# AMP.net
KiCad netlist of a schematic drawn in Altium Designer
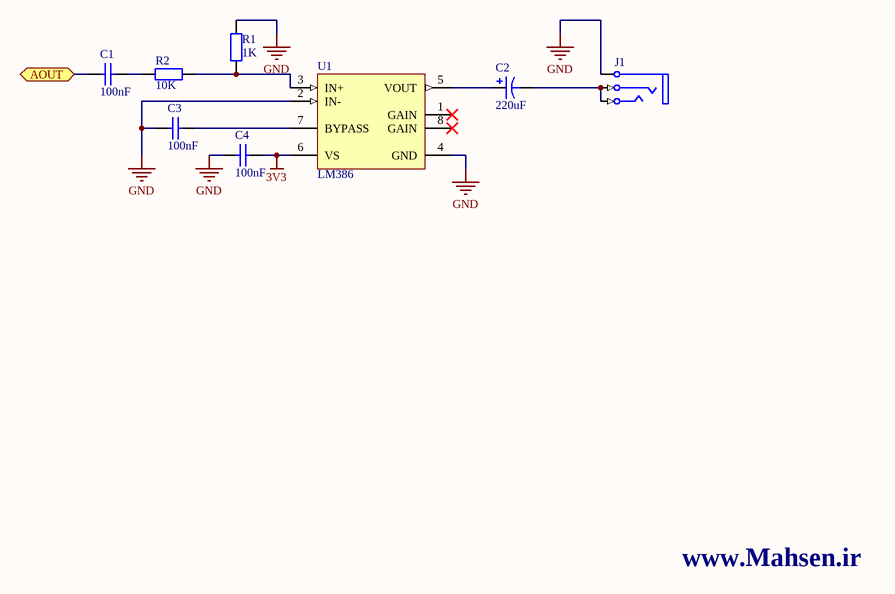
[diagram p0: AMP.SchDoc]

(export (version "E")
  (design (tool "Eeschema 10.0.6"))
  (components
    (comp (ref "C1")
      (value "100nF")
      (footprint "0805")
      (description "Capacitor")
      (fields (field (name "PUBLISHER") "Altium Limited"))
      (libsource (lib "Miscellaneous Devices") (part "Cap"))
    )
    (comp (ref "C2")
      (value "220uF")
      (footprint "CAPR5-4X5")
      (description "Polarized Capacitor (Surface Mount)")
      (fields (field (name "PUBLISHER") "Altium Limited"))
      (libsource (lib "Miscellaneous Devices") (part "Cap Pol3"))
    )
    (comp (ref "C3")
      (value "100nF")
      (footprint "0805")
      (description "Capacitor")
      (fields (field (name "PUBLISHER") "Altium Limited"))
      (libsource (lib "Miscellaneous Devices") (part "Cap"))
    )
    (comp (ref "C4")
      (value "100nF")
      (footprint "0805")
      (description "Capacitor")
      (fields (field (name "PUBLISHER") "Altium Limited"))
      (libsource (lib "Miscellaneous Devices") (part "Cap"))
    )
    (comp (ref "J1")
      (value "Phonejack3")
      (footprint "KLD-0202")
      (description "Jack Socket, 1/4\" [6.5mm], Thru-Hole, Vertical, 3-Conductor Open Circuit (Non-Normalling)")
      (fields (field (name "PUBLISHER") "Altium Limited"))
      (libsource (lib "Miscellaneous Connectors") (part "Phonejack3"))
    )
    (comp (ref "R1")
      (value "1K")
      (footprint "0805")
      (description "Resistor")
      (fields (field (name "PUBLISHER") "Altium Limited"))
      (libsource (lib "") (part "Res2_1"))
    )
    (comp (ref "R2")
      (value "10K")
      (footprint "0805")
      (description "Resistor")
      (fields (field (name "PUBLISHER") "Altium Limited"))
      (libsource (lib "Miscellaneous Devices") (part "Res2"))
    )
    (comp (ref "U1")
      (value "LM386")
      (footprint "M08A_L")
      (description "Low Voltage Audio Power Amplifier, 8-pin Narrow SOIC")
      (fields
        (field (name "PARTNUMBER") "LM386MX-1")
        (field (name "MANUFACTURER") "National Semiconductor")
        (field (name "PUBLISHER") "Altium Limited")
      )
      (libsource (lib "NSC Audio") (part "LM386MX-1"))
    )
  )
  (nets
    (net (code "1") (name "/AOUT") (class "Default")
      (node (ref "C1") (pin "2") (pinfunction "2_2") (pintype "passive"))
    )
    (net (code "2") (name "3V3") (class "Default")
      (node (ref "C4") (pin "1") (pinfunction "1_1") (pintype "passive"))
      (node (ref "U1") (pin "6") (pinfunction "VS_6") (pintype "power_in"))
    )
    (net (code "3") (name "GND") (class "Default")
      (node (ref "C3") (pin "2") (pinfunction "2_2") (pintype "passive"))
      (node (ref "C4") (pin "2") (pinfunction "2_2") (pintype "passive"))
      (node (ref "J1") (pin "5") (pinfunction "S_5") (pintype "power_in"))
      (node (ref "R1") (pin "2") (pinfunction "2_2") (pintype "passive"))
      (node (ref "U1") (pin "2") (pinfunction "IN-_2") (pintype "input"))
      (node (ref "U1") (pin "4") (pinfunction "GND_4") (pintype "power_in"))
    )
    (net (code "4") (name "Net-(C1-Pad1)") (class "Default")
      (node (ref "C1") (pin "1") (pinfunction "1_1") (pintype "passive"))
      (node (ref "R2") (pin "1") (pinfunction "1_1") (pintype "passive"))
    )
    (net (code "5") (name "Net-(J1-R)") (class "Default")
      (node (ref "C2") (pin "2") (pinfunction "2_2") (pintype "passive"))
      (node (ref "J1") (pin "1") (pinfunction "T_1") (pintype "input"))
      (node (ref "J1") (pin "3") (pinfunction "R_3") (pintype "input"))
    )
    (net (code "6") (name "Net-(U1-BYPASS)") (class "Default")
      (node (ref "C3") (pin "1") (pinfunction "1_1") (pintype "passive"))
      (node (ref "U1") (pin "7") (pinfunction "BYPASS_7") (pintype "passive"))
    )
    (net (code "7") (name "Net-(U1-IN+)") (class "Default")
      (node (ref "R1") (pin "1") (pinfunction "1_1") (pintype "passive"))
      (node (ref "R2") (pin "2") (pinfunction "2_2") (pintype "passive"))
      (node (ref "U1") (pin "3") (pinfunction "IN+_3") (pintype "input"))
    )
    (net (code "8") (name "Net-(U1-VOUT)") (class "Default")
      (node (ref "C2") (pin "1") (pinfunction "1_1") (pintype "passive"))
      (node (ref "U1") (pin "5") (pinfunction "VOUT_5") (pintype "output"))
    )
    (net (code "9") (name "unconnected-(U1-GAIN-Pad1)") (class "Default")
      (node (ref "U1") (pin "1") (pinfunction "GAIN_1") (pintype "passive+no_connect"))
    )
    (net (code "10") (name "unconnected-(U1-GAIN-Pad8)") (class "Default")
      (node (ref "U1") (pin "8") (pinfunction "GAIN_8") (pintype "passive+no_connect"))
    )
  )
)
